# 5kW_Sensor.net
KiCad netlist of a schematic drawn in Altium Designer
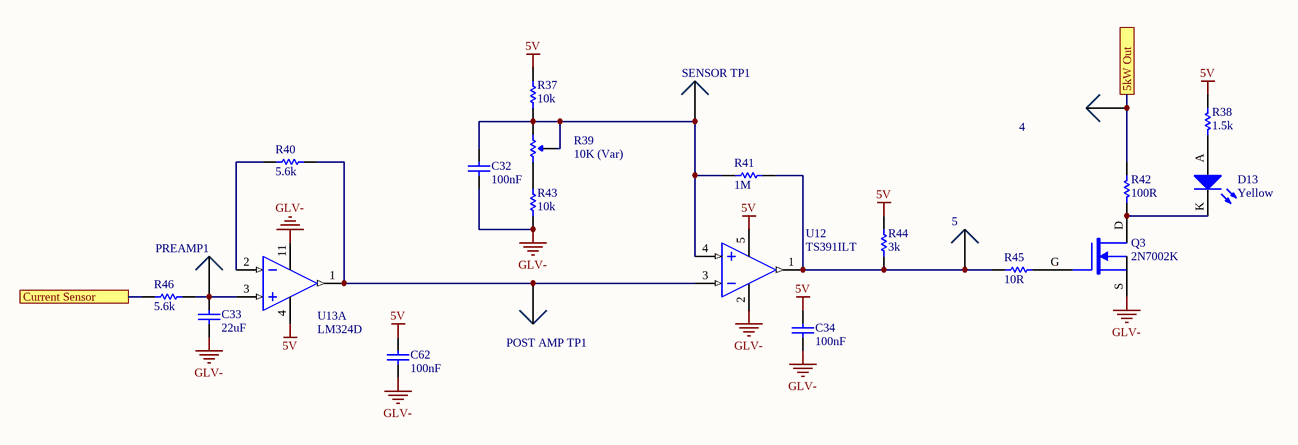
[diagram p0: 5kW Sensor.SchDoc]

(export (version "E")
  (design (tool "Eeschema 10.0.6"))
  (components
    (comp (ref "4")
      (value "0mm")
      (footprint "TH Test Point")
      (fields (field (name "PART NUMBER") "TH Test Point") (field (name "CONTACT") "NA"))
      (libsource (lib "ts_20-standard-connectors") (part "Test Point"))
    )
    (comp (ref "5")
      (value "0mm")
      (footprint "TH Test Point")
      (fields (field (name "PART NUMBER") "TH Test Point") (field (name "CONTACT") "NA"))
      (libsource (lib "ts_20-standard-connectors") (part "Test Point"))
    )
    (comp (ref "C32")
      (value "100nF")
      (footprint "0805")
      (fields
        (field (name "PART NUMBER") "GCM21BR71E104KA37L")
        (field (name "TOLERANCE") "10%")
        (field (name "MANUFACTURER") "muRata")
      )
      (libsource (lib "ts_20-standard-library") (part "Capacitor"))
    )
    (comp (ref "C33")
      (value "22uF")
      (footprint "0805")
      (fields
        (field (name "PART NUMBER") "GRM21BR61A226ME51L")
        (field (name "TOLERANCE") "20%")
        (field (name "MANUFACTURER") "muRata")
      )
      (libsource (lib "ts_20-standard-library") (part "Capacitor"))
    )
    (comp (ref "C34")
      (value "100nF")
      (footprint "0805")
      (fields
        (field (name "PART NUMBER") "GCM21BR71E104KA37L")
        (field (name "TOLERANCE") "10%")
        (field (name "MANUFACTURER") "muRata")
      )
      (libsource (lib "ts_20-standard-library") (part "Capacitor"))
    )
    (comp (ref "C62")
      (value "100nF")
      (footprint "0805")
      (fields
        (field (name "PART NUMBER") "GCM21BR71E104KA37L")
        (field (name "TOLERANCE") "10%")
        (field (name "MANUFACTURER") "muRata")
      )
      (libsource (lib "ts_20-standard-library") (part "Capacitor"))
    )
    (comp (ref "D13")
      (value "Yellow")
      (footprint "0805 LED")
      (description "Yellow LED Indication - Discrete 1.75V 0805 (2012 Metric)")
      (fields (field (name "PART NUMBER") "SML-211YTT86") (field (name "MANUFACTURER") "ROHM Semiconductor"))
      (libsource (lib "ts_20-standard-library") (part "LED"))
    )
    (comp (ref "POST AMP TP1")
      (value "0mm")
      (footprint "TH Test Point")
      (fields (field (name "PART NUMBER") "TH Test Point") (field (name "CONTACT") "NA"))
      (libsource (lib "ts_20-standard-connectors") (part "Test Point"))
    )
    (comp (ref "PREAMP1")
      (value "0mm")
      (footprint "TH Test Point")
      (fields (field (name "PART NUMBER") "TH Test Point") (field (name "CONTACT") "NA"))
      (libsource (lib "ts_20-standard-connectors") (part "Test Point"))
    )
    (comp (ref "Q3")
      (value "2N7002K")
      (footprint "ON SOT-23 MOSFET")
      (description "60V 380mA, NFET MOSTFET (Small Signal)")
      (fields
        (field (name "MANUFACTURER") "ON Semiconductor")
        (field (name "DIGIKEY PART NUMBER") "2N7002KCT-ND")
        (field (name "PUBLISHER") "Altium Limited")
      )
      (libsource (lib "ts_20-standard-library") (part "MOSFET-N"))
    )
    (comp (ref "R37")
      (value "10k")
      (footprint "0805")
      (fields
        (field (name "PART NUMBER") "RC0805FR0710KL")
        (field (name "MANUFACTURER") "YAGEO")
        (field (name "TOLERANCE") "0.01")
      )
      (libsource (lib "ts_20-standard-library") (part "Resistor"))
    )
    (comp (ref "R38")
      (value "1.5k")
      (footprint "0805")
      (fields
        (field (name "PART NUMBER") "RC0805FR071K5L")
        (field (name "MANUFACTURER") "YAGEO")
        (field (name "TOLERANCE") "0.01")
      )
      (libsource (lib "ts_20-standard-library") (part "Resistor"))
    )
    (comp (ref "R39")
      (value "10K (Var)")
      (footprint "B 3296")
      (fields
        (field (name "PART NUMBER") "3296W-1-103LF")
        (field (name "MANUFACTURER") "Bournes Inc")
        (field (name "TOLERANCE") "0.1")
      )
      (libsource (lib "ts_20-standard-library") (part "Resistor (Potentiometer)"))
    )
    (comp (ref "R40")
      (value "5.6k")
      (footprint "0805")
      (fields
        (field (name "PART NUMBER") "RC0805FR075K6L")
        (field (name "MANUFACTURER") "YAGEO")
        (field (name "TOLERANCE") "0.01")
      )
      (libsource (lib "ts_20-standard-library") (part "Resistor"))
    )
    (comp (ref "R41")
      (value "1M")
      (footprint "0805")
      (fields
        (field (name "PART NUMBER") "RC0805FR071ML")
        (field (name "MANUFACTURER") "YAGEO")
        (field (name "TOLERANCE") "0.01")
      )
      (libsource (lib "ts_20-standard-library") (part "Resistor"))
    )
    (comp (ref "R42")
      (value "100R")
      (footprint "0805")
      (fields
        (field (name "PART NUMBER") "RC0805FR07100RL")
        (field (name "MANUFACTURER") "YAGEO")
        (field (name "TOLERANCE") "0.01")
      )
      (libsource (lib "ts_20-standard-library") (part "Resistor"))
    )
    (comp (ref "R43")
      (value "10k")
      (footprint "0805")
      (fields
        (field (name "PART NUMBER") "RC0805FR0710KL")
        (field (name "MANUFACTURER") "YAGEO")
        (field (name "TOLERANCE") "0.01")
      )
      (libsource (lib "ts_20-standard-library") (part "Resistor"))
    )
    (comp (ref "R44")
      (value "3k")
      (footprint "0805")
      (fields
        (field (name "PART NUMBER") "RC0805FR073KL")
        (field (name "MANUFACTURER") "YAGEO")
        (field (name "TOLERANCE") "0.01")
      )
      (libsource (lib "ts_20-standard-library") (part "Resistor"))
    )
    (comp (ref "R45")
      (value "10R")
      (footprint "0805")
      (fields
        (field (name "PART NUMBER") "RC0805FR0710RL")
        (field (name "MANUFACTURER") "YAGEO")
        (field (name "TOLERANCE") "0.01")
      )
      (libsource (lib "ts_20-standard-library") (part "Resistor"))
    )
    (comp (ref "R46")
      (value "5.6k")
      (footprint "0805")
      (fields
        (field (name "PART NUMBER") "RC0805FR075K6L")
        (field (name "MANUFACTURER") "YAGEO")
        (field (name "TOLERANCE") "0.01")
      )
      (libsource (lib "ts_20-standard-library") (part "Resistor"))
    )
    (comp (ref "SENSOR TP1")
      (value "0mm")
      (footprint "TH Test Point")
      (fields (field (name "PART NUMBER") "TH Test Point") (field (name "CONTACT") "NA"))
      (libsource (lib "ts_20-standard-connectors") (part "Test Point"))
    )
    (comp (ref "U12")
      (value "TS391ILT")
      (footprint "ON SOT-23-5")
      (description "IC COMP LO PWR SGL V SOT 23-5L")
      (fields
        (field (name "MANUFACTURER") "STMicroelectronics")
        (field (name "DIGIKEY PART NUMBER") "497-2275-2-ND")
      )
      (libsource (lib "ts_20-standard-library") (part "TS391ILT"))
    )
    (comp (ref "U13")
      (value "LM324D")
      (footprint "TI 14-SOIC")
      (description "IC OPAMP GP 4 CIRCUIT 14SOIC")
      (fields
        (field (name "MANUFACTURER") "Texas Instruments")
        (field (name "DIGIKEY PART NUMBER") "296-1390-5-ND")
      )
      (libsource (lib "ts_20-standard-library") (part "LM324D"))
    )
  )
  (nets
    (net (code "1") (name "/5kW Out") (class "Default")
      (node (ref "4") (pin "1") (pinfunction "1_1") (pintype "passive"))
      (node (ref "R42") (pin "2") (pinfunction "2_2") (pintype "passive"))
    )
    (net (code "2") (name "/Current Sensor") (class "Default")
      (node (ref "R46") (pin "1") (pinfunction "1_1") (pintype "passive"))
    )
    (net (code "3") (name "5V") (class "Default")
      (node (ref "C34") (pin "2") (pinfunction "2_2") (pintype "passive"))
      (node (ref "C62") (pin "2") (pinfunction "2_2") (pintype "passive"))
      (node (ref "R37") (pin "2") (pinfunction "2_2") (pintype "passive"))
      (node (ref "R38") (pin "2") (pinfunction "2_2") (pintype "passive"))
      (node (ref "R44") (pin "2") (pinfunction "2_2") (pintype "passive"))
      (node (ref "U12") (pin "5") (pinfunction "VCC+_5") (pintype "power_in"))
      (node (ref "U13") (pin "4") (pinfunction "VCC_4") (pintype "power_in"))
    )
    (net (code "4") (name "GLV-") (class "Default")
      (node (ref "C32") (pin "1") (pinfunction "1_1") (pintype "passive"))
      (node (ref "C33") (pin "1") (pinfunction "1_1") (pintype "passive"))
      (node (ref "C34") (pin "1") (pinfunction "1_1") (pintype "passive"))
      (node (ref "C62") (pin "1") (pinfunction "1_1") (pintype "passive"))
      (node (ref "Q3") (pin "S") (pinfunction "S_S") (pintype "passive"))
      (node (ref "R43") (pin "1") (pinfunction "1_1") (pintype "passive"))
      (node (ref "U12") (pin "2") (pinfunction "VCC-_2") (pintype "power_in"))
      (node (ref "U13") (pin "11") (pinfunction "GND_11") (pintype "power_in"))
    )
    (net (code "5") (name "Net-(C33-Pad2)") (class "Default")
      (node (ref "C33") (pin "2") (pinfunction "2_2") (pintype "passive"))
      (node (ref "PREAMP1") (pin "1") (pinfunction "1_1") (pintype "passive"))
      (node (ref "R46") (pin "2") (pinfunction "2_2") (pintype "passive"))
      (node (ref "U13") (pin "3") (pinfunction "1IN+_3") (pintype "input"))
    )
    (net (code "6") (name "Net-(D13-PadA)") (class "Default")
      (node (ref "D13") (pin "A") (pinfunction "A_A") (pintype "passive"))
      (node (ref "R38") (pin "1") (pinfunction "1_1") (pintype "passive"))
    )
    (net (code "7") (name "Net-(D13-PadK)") (class "Default")
      (node (ref "D13") (pin "K") (pinfunction "K_K") (pintype "passive"))
      (node (ref "Q3") (pin "D") (pinfunction "D_D") (pintype "passive"))
      (node (ref "R42") (pin "1") (pinfunction "1_1") (pintype "passive"))
    )
    (net (code "8") (name "Net-(Q3-PadG)") (class "Default")
      (node (ref "Q3") (pin "G") (pinfunction "G_G") (pintype "passive"))
      (node (ref "R45") (pin "2") (pinfunction "2_2") (pintype "passive"))
    )
    (net (code "9") (name "Net-(R39-CCW)") (class "Default")
      (node (ref "C32") (pin "2") (pinfunction "2_2") (pintype "passive"))
      (node (ref "R37") (pin "1") (pinfunction "1_1") (pintype "passive"))
      (node (ref "R39") (pin "1") (pinfunction "CCW_1") (pintype "passive"))
      (node (ref "R39") (pin "2") (pinfunction "Wiper_2") (pintype "passive"))
      (node (ref "R41") (pin "1") (pinfunction "1_1") (pintype "passive"))
      (node (ref "SENSOR TP1") (pin "1") (pinfunction "1_1") (pintype "passive"))
      (node (ref "U12") (pin "4") (pinfunction "IIN+_4") (pintype "input"))
    )
    (net (code "10") (name "Net-(R39-CW)") (class "Default")
      (node (ref "R39") (pin "3") (pinfunction "CW_3") (pintype "passive"))
      (node (ref "R43") (pin "2") (pinfunction "2_2") (pintype "passive"))
    )
    (net (code "11") (name "Net-(R40-Pad1)") (class "Default")
      (node (ref "R40") (pin "1") (pinfunction "1_1") (pintype "passive"))
      (node (ref "U13") (pin "2") (pinfunction "1IN+_2") (pintype "input"))
    )
    (net (code "12") (name "Net-(U12-IN-)") (class "Default")
      (node (ref "POST AMP TP1") (pin "1") (pinfunction "1_1") (pintype "passive"))
      (node (ref "R40") (pin "2") (pinfunction "2_2") (pintype "passive"))
      (node (ref "U12") (pin "3") (pinfunction "IN-_3") (pintype "input"))
      (node (ref "U13") (pin "1") (pinfunction "1OUT_1") (pintype "output"))
    )
    (net (code "13") (name "Net-(U12-OUT)") (class "Default")
      (node (ref "5") (pin "1") (pinfunction "1_1") (pintype "passive"))
      (node (ref "R41") (pin "2") (pinfunction "2_2") (pintype "passive"))
      (node (ref "R44") (pin "1") (pinfunction "1_1") (pintype "passive"))
      (node (ref "R45") (pin "1") (pinfunction "1_1") (pintype "passive"))
      (node (ref "U12") (pin "1") (pinfunction "OUT_1") (pintype "output"))
    )
  )
)
